# Switch.net
KiCad netlist of a schematic drawn in Altium Designer
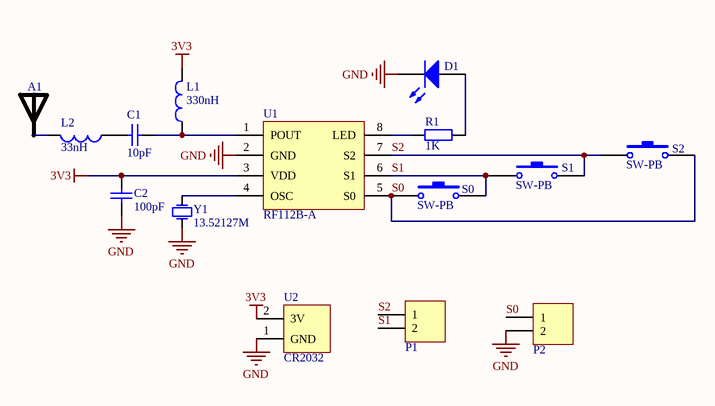
[diagram p0: Switch.SchDoc]

(export (version "E")
  (design (tool "Eeschema 10.0.6"))
  (components
    (comp (ref "A1")
      (value "ANT")
      (footprint "PCBPcblib_SEU_RobotLab:ANT15030R433")
      (libsource (lib "PCBSchlib_SEU_RobotLab") (part "ANT"))
    )
    (comp (ref "C1")
      (value "10pF")
      (footprint "0603-2")
      (description "无极性电容")
      (fields (field (name "Comment") "Cap") (field (name "PUBLISHER") "Altium Limited"))
      (libsource (lib "PCBSchlib_SEU_RobotLab") (part "Cap"))
    )
    (comp (ref "C2")
      (value "100pF")
      (footprint "0603-2")
      (description "无极性电容")
      (fields (field (name "Comment") "Cap") (field (name "PUBLISHER") "Altium Limited"))
      (libsource (lib "PCBSchlib_SEU_RobotLab") (part "Cap"))
    )
    (comp (ref "D1")
      (value "LED0")
      (footprint "LED_0603")
      (description "发光二极管")
      (fields (field (name "PUBLISHER") "Altium Limited"))
      (libsource (lib "PCBSchlib_SEU_RobotLab") (part "LED0"))
    )
    (comp (ref "L1")
      (value "330nH")
      (footprint "PCBPcblib_SEU_RobotLab:0603-1")
      (description "电感")
      (fields (field (name "Comment") "Inductor") (field (name "PUBLISHER") "Altium Limited"))
      (libsource (lib "PCBSchlib_SEU_RobotLab") (part "Inductor"))
    )
    (comp (ref "L2")
      (value "33nH")
      (footprint "PCBPcblib_SEU_RobotLab:0603-1")
      (description "电感")
      (fields (field (name "Comment") "Inductor") (field (name "PUBLISHER") "Altium Limited"))
      (libsource (lib "PCBSchlib_SEU_RobotLab") (part "Inductor"))
    )
    (comp (ref "P1")
      (value "Header 2")
      (footprint "PCBPcblib_SEU_RobotLab:HDR2X1_焊接版")
      (description "接插件")
      (fields (field (name "PUBLISHER") "Altium Limited"))
      (libsource (lib "PCBSchlib_SEU_RobotLab") (part "Header 2"))
    )
    (comp (ref "P2")
      (value "Header 2")
      (footprint "PCBPcblib_SEU_RobotLab:HDR2X1_焊接版")
      (description "接插件")
      (fields (field (name "PUBLISHER") "Altium Limited"))
      (libsource (lib "PCBSchlib_SEU_RobotLab") (part "Header 2"))
    )
    (comp (ref "R1")
      (value "1K")
      (footprint "0603-1")
      (description "贴片电阻")
      (fields (field (name "Comment") "12K") (field (name "PUBLISHER") "Altium Limited"))
      (libsource (lib "PCBSchlib_SEU_RobotLab") (part "Res1"))
    )
    (comp (ref "S0")
      (value "SW-PB")
      (footprint "SW_PB2_A1")
      (description "微动开关")
      (fields (field (name "PUBLISHER") "Altium Limited"))
      (libsource (lib "PCBSchlib_SEU_RobotLab") (part "SW-PB"))
    )
    (comp (ref "S1")
      (value "SW-PB")
      (footprint "SW_PB2_A1")
      (description "微动开关")
      (fields (field (name "PUBLISHER") "Altium Limited"))
      (libsource (lib "PCBSchlib_SEU_RobotLab") (part "SW-PB"))
    )
    (comp (ref "S2")
      (value "SW-PB")
      (footprint "SW_PB2_A1")
      (description "微动开关")
      (fields (field (name "PUBLISHER") "Altium Limited"))
      (libsource (lib "PCBSchlib_SEU_RobotLab") (part "SW-PB"))
    )
    (comp (ref "U1")
      (value "RF112B-A")
      (footprint "PCBPcblib_SEU_RobotLab:SOIC-8")
      (description "内置编码无线发射芯片")
      (libsource (lib "PCBSchlib_SEU_RobotLab") (part "RF112B-A"))
    )
    (comp (ref "U2")
      (value "CR2032")
      (footprint "PCBPcblib_SEU_RobotLab:CR2032-SMD")
      (description "纽扣电池座")
      (libsource (lib "PCBSchlib_SEU_RobotLab") (part "CR2032"))
    )
    (comp (ref "Y1")
      (value "13.52127M")
      (footprint "X-SM49")
      (description "晶振")
      (fields (field (name "Comment") "XTAL") (field (name "PUBLISHER") "Altium Limited"))
      (libsource (lib "PCBSchlib_SEU_RobotLab") (part "XTAL"))
    )
  )
  (nets
    (net (code "1") (name "/S0") (class "Default")
      (node (ref "P2") (pin "1") (pinfunction "1_1") (pintype "passive"))
      (node (ref "S0") (pin "1") (pinfunction "1_1") (pintype "passive"))
      (node (ref "S2") (pin "2") (pinfunction "2_2") (pintype "passive"))
      (node (ref "U1") (pin "5") (pinfunction "S0_5") (pintype "passive"))
    )
    (net (code "2") (name "/S1") (class "Default")
      (node (ref "P1") (pin "2") (pinfunction "2_2") (pintype "passive"))
      (node (ref "S0") (pin "2") (pinfunction "2_2") (pintype "passive"))
      (node (ref "S1") (pin "1") (pinfunction "1_1") (pintype "passive"))
      (node (ref "U1") (pin "6") (pinfunction "S1_6") (pintype "passive"))
    )
    (net (code "3") (name "/S2") (class "Default")
      (node (ref "P1") (pin "1") (pinfunction "1_1") (pintype "passive"))
      (node (ref "S1") (pin "2") (pinfunction "2_2") (pintype "passive"))
      (node (ref "S2") (pin "1") (pinfunction "1_1") (pintype "passive"))
      (node (ref "U1") (pin "7") (pinfunction "S2_7") (pintype "passive"))
    )
    (net (code "4") (name "3V3") (class "Default")
      (node (ref "C2") (pin "2") (pinfunction "2_2") (pintype "passive"))
      (node (ref "L1") (pin "2") (pinfunction "2_2") (pintype "passive"))
      (node (ref "U1") (pin "3") (pinfunction "VDD_3") (pintype "passive"))
      (node (ref "U2") (pin "2") (pinfunction "3V_2") (pintype "passive"))
    )
    (net (code "5") (name "GND") (class "Default")
      (node (ref "C2") (pin "1") (pinfunction "1_1") (pintype "passive"))
      (node (ref "D1") (pin "2") (pinfunction "K_2") (pintype "passive"))
      (node (ref "P2") (pin "2") (pinfunction "2_2") (pintype "passive"))
      (node (ref "U1") (pin "2") (pinfunction "GND_2") (pintype "passive"))
      (node (ref "U2") (pin "1") (pinfunction "GND_1") (pintype "passive"))
      (node (ref "Y1") (pin "1") (pinfunction "1_1") (pintype "passive"))
    )
    (net (code "6") (name "Net-(A1-Pad1)") (class "Default")
      (node (ref "A1") (pin "1") (pinfunction "1_1") (pintype "passive"))
      (node (ref "L2") (pin "2") (pinfunction "2_2") (pintype "passive"))
    )
    (net (code "7") (name "Net-(C1-Pad1)") (class "Default")
      (node (ref "C1") (pin "1") (pinfunction "1_1") (pintype "passive"))
      (node (ref "L2") (pin "1") (pinfunction "1_1") (pintype "passive"))
    )
    (net (code "8") (name "Net-(D1-A)") (class "Default")
      (node (ref "D1") (pin "1") (pinfunction "A_1") (pintype "passive"))
      (node (ref "R1") (pin "1") (pinfunction "1_1") (pintype "passive"))
    )
    (net (code "9") (name "Net-(U1-LED)") (class "Default")
      (node (ref "R1") (pin "2") (pinfunction "2_2") (pintype "passive"))
      (node (ref "U1") (pin "8") (pinfunction "LED_8") (pintype "passive"))
    )
    (net (code "10") (name "Net-(U1-OSC)") (class "Default")
      (node (ref "U1") (pin "4") (pinfunction "OSC_4") (pintype "passive"))
      (node (ref "Y1") (pin "2") (pinfunction "2_2") (pintype "passive"))
    )
    (net (code "11") (name "Net-(U1-POUT)") (class "Default")
      (node (ref "C1") (pin "2") (pinfunction "2_2") (pintype "passive"))
      (node (ref "L1") (pin "1") (pinfunction "1_1") (pintype "passive"))
      (node (ref "U1") (pin "1") (pinfunction "POUT_1") (pintype "passive"))
    )
  )
)
